# Small_DDS.net
KiCad netlist of a schematic drawn in Altium Designer
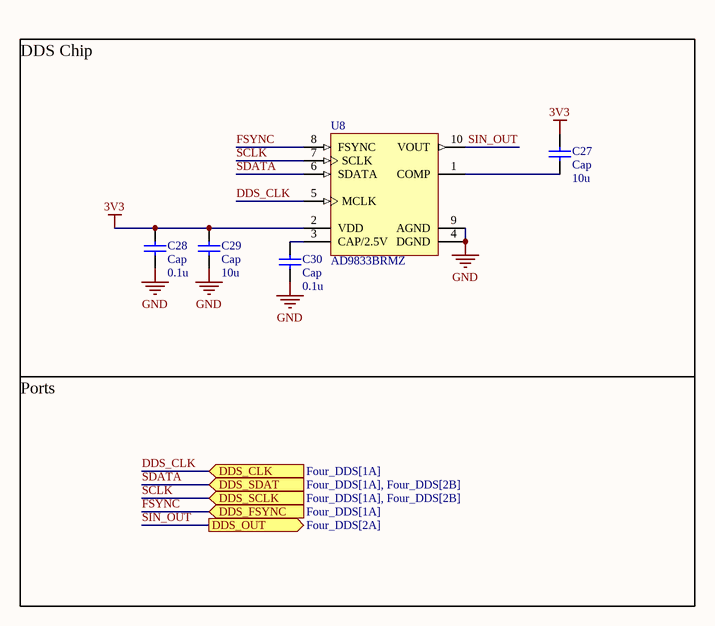
[diagram p0: Small_DDS.SchDoc]

(export (version "E")
  (design (tool "Eeschema 10.0.6"))
  (components
    (comp (ref "C27")
      (value "Cap")
      (footprint "0402_Res")
      (description "Capacitor")
      (fields (field (name "ALTIUM_VALUE") "10u") (field (name "PUBLISHER") "Altium Limited"))
      (libsource (lib "Miscellaneous Devices") (part "Cap"))
    )
    (comp (ref "C28")
      (value "Cap")
      (footprint "0402_Res")
      (description "Capacitor")
      (fields (field (name "ALTIUM_VALUE") "0.1u") (field (name "PUBLISHER") "Altium Limited"))
      (libsource (lib "Miscellaneous Devices") (part "Cap"))
    )
    (comp (ref "C29")
      (value "Cap")
      (footprint "0402_Res")
      (description "Capacitor")
      (fields (field (name "ALTIUM_VALUE") "10u") (field (name "PUBLISHER") "Altium Limited"))
      (libsource (lib "Miscellaneous Devices") (part "Cap"))
    )
    (comp (ref "C30")
      (value "Cap")
      (footprint "0402_Res")
      (description "Capacitor")
      (fields (field (name "ALTIUM_VALUE") "0.1u") (field (name "PUBLISHER") "Altium Limited"))
      (libsource (lib "Miscellaneous Devices") (part "Cap"))
    )
    (comp (ref "U8")
      (value "AD9833BRMZ")
      (footprint "ADI-RM-10_M")
      (libsource (lib "Altium Content Vault") (part "ADI-AD9833-RM-10"))
    )
  )
  (nets
    (net (code "1") (name "/DDS_CLK") (class "Default")
      (node (ref "U8") (pin "5") (pinfunction "MCLK_5") (pintype "input"))
    )
    (net (code "2") (name "/FSYNC") (class "Default")
      (node (ref "U8") (pin "8") (pinfunction "FSYNC_8") (pintype "input"))
    )
    (net (code "3") (name "/SCLK") (class "Default")
      (node (ref "U8") (pin "7") (pinfunction "SCLK_7") (pintype "input"))
    )
    (net (code "4") (name "/SDATA") (class "Default")
      (node (ref "U8") (pin "6") (pinfunction "SDATA_6") (pintype "input"))
    )
    (net (code "5") (name "/SIN_OUT") (class "Default")
      (node (ref "U8") (pin "10") (pinfunction "VOUT_10") (pintype "output"))
    )
    (net (code "6") (name "3V3") (class "Default")
      (node (ref "C27") (pin "2") (pinfunction "2_2") (pintype "passive"))
      (node (ref "C28") (pin "2") (pinfunction "2_2") (pintype "passive"))
      (node (ref "C29") (pin "2") (pinfunction "2_2") (pintype "passive"))
      (node (ref "U8") (pin "2") (pinfunction "VDD_2") (pintype "power_in"))
    )
    (net (code "7") (name "GND") (class "Default")
      (node (ref "C28") (pin "1") (pinfunction "1_1") (pintype "passive"))
      (node (ref "C29") (pin "1") (pinfunction "1_1") (pintype "passive"))
      (node (ref "C30") (pin "1") (pinfunction "1_1") (pintype "passive"))
      (node (ref "U8") (pin "4") (pinfunction "DGND_4") (pintype "power_in"))
      (node (ref "U8") (pin "9") (pinfunction "AGND_9") (pintype "power_in"))
    )
    (net (code "8") (name "Net-(U8-CAP{slash}2.5V)") (class "Default")
      (node (ref "C30") (pin "2") (pinfunction "2_2") (pintype "passive"))
      (node (ref "U8") (pin "3") (pinfunction "CAP/2.5V_3") (pintype "power_in"))
    )
    (net (code "9") (name "Net-(U8-COMP)") (class "Default")
      (node (ref "C27") (pin "1") (pinfunction "1_1") (pintype "passive"))
      (node (ref "U8") (pin "1") (pinfunction "COMP_1") (pintype "passive"))
    )
  )
)
